# noise_monitor.net
KiCad netlist of a schematic drawn in EAGLE
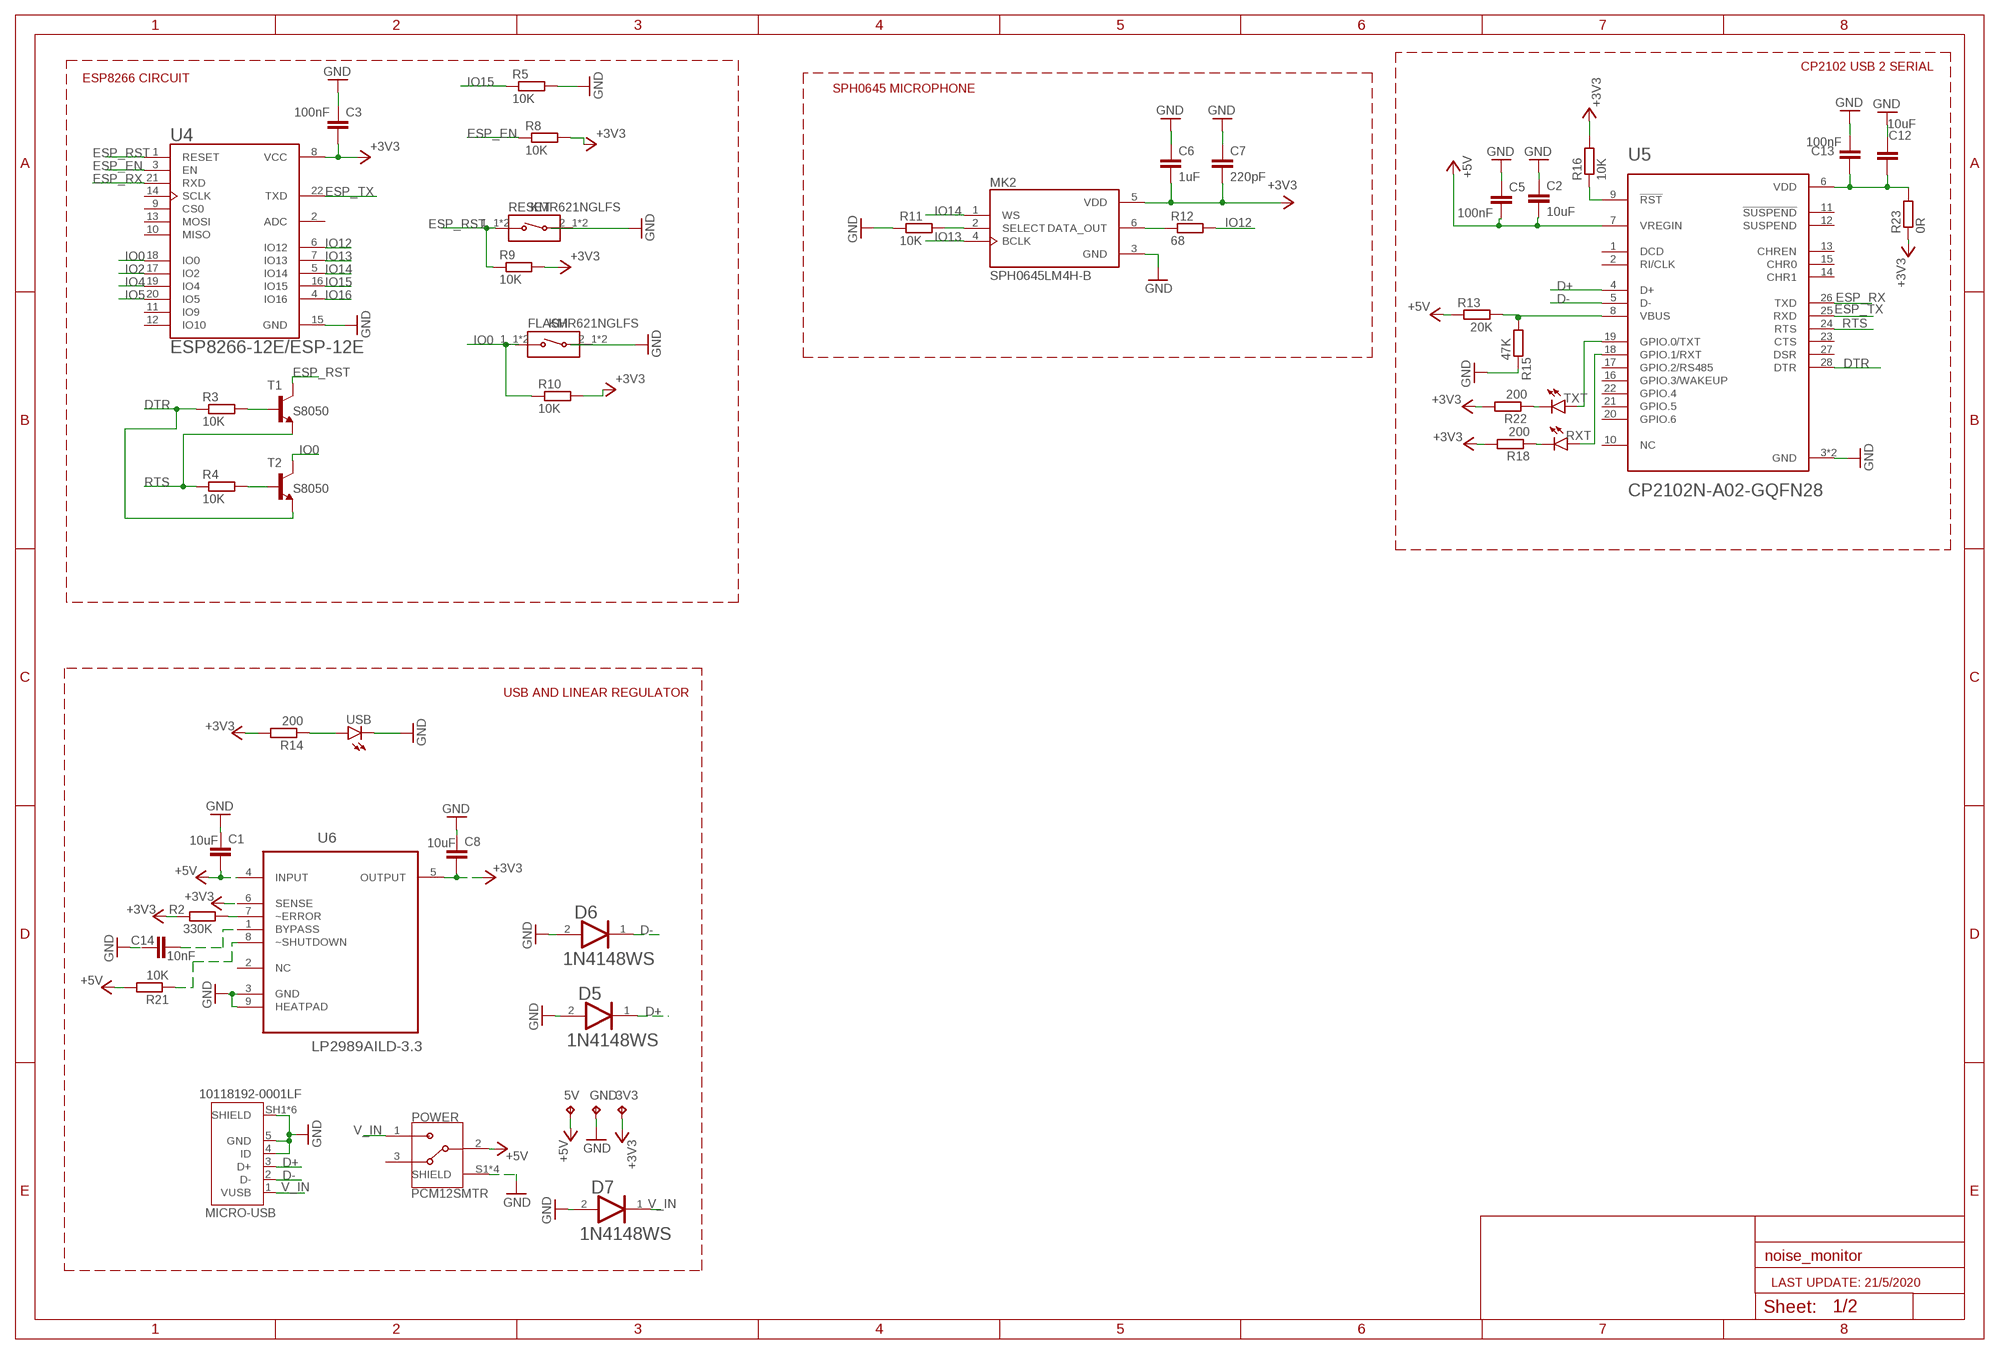
[diagram p0: schematic, sheet 1]
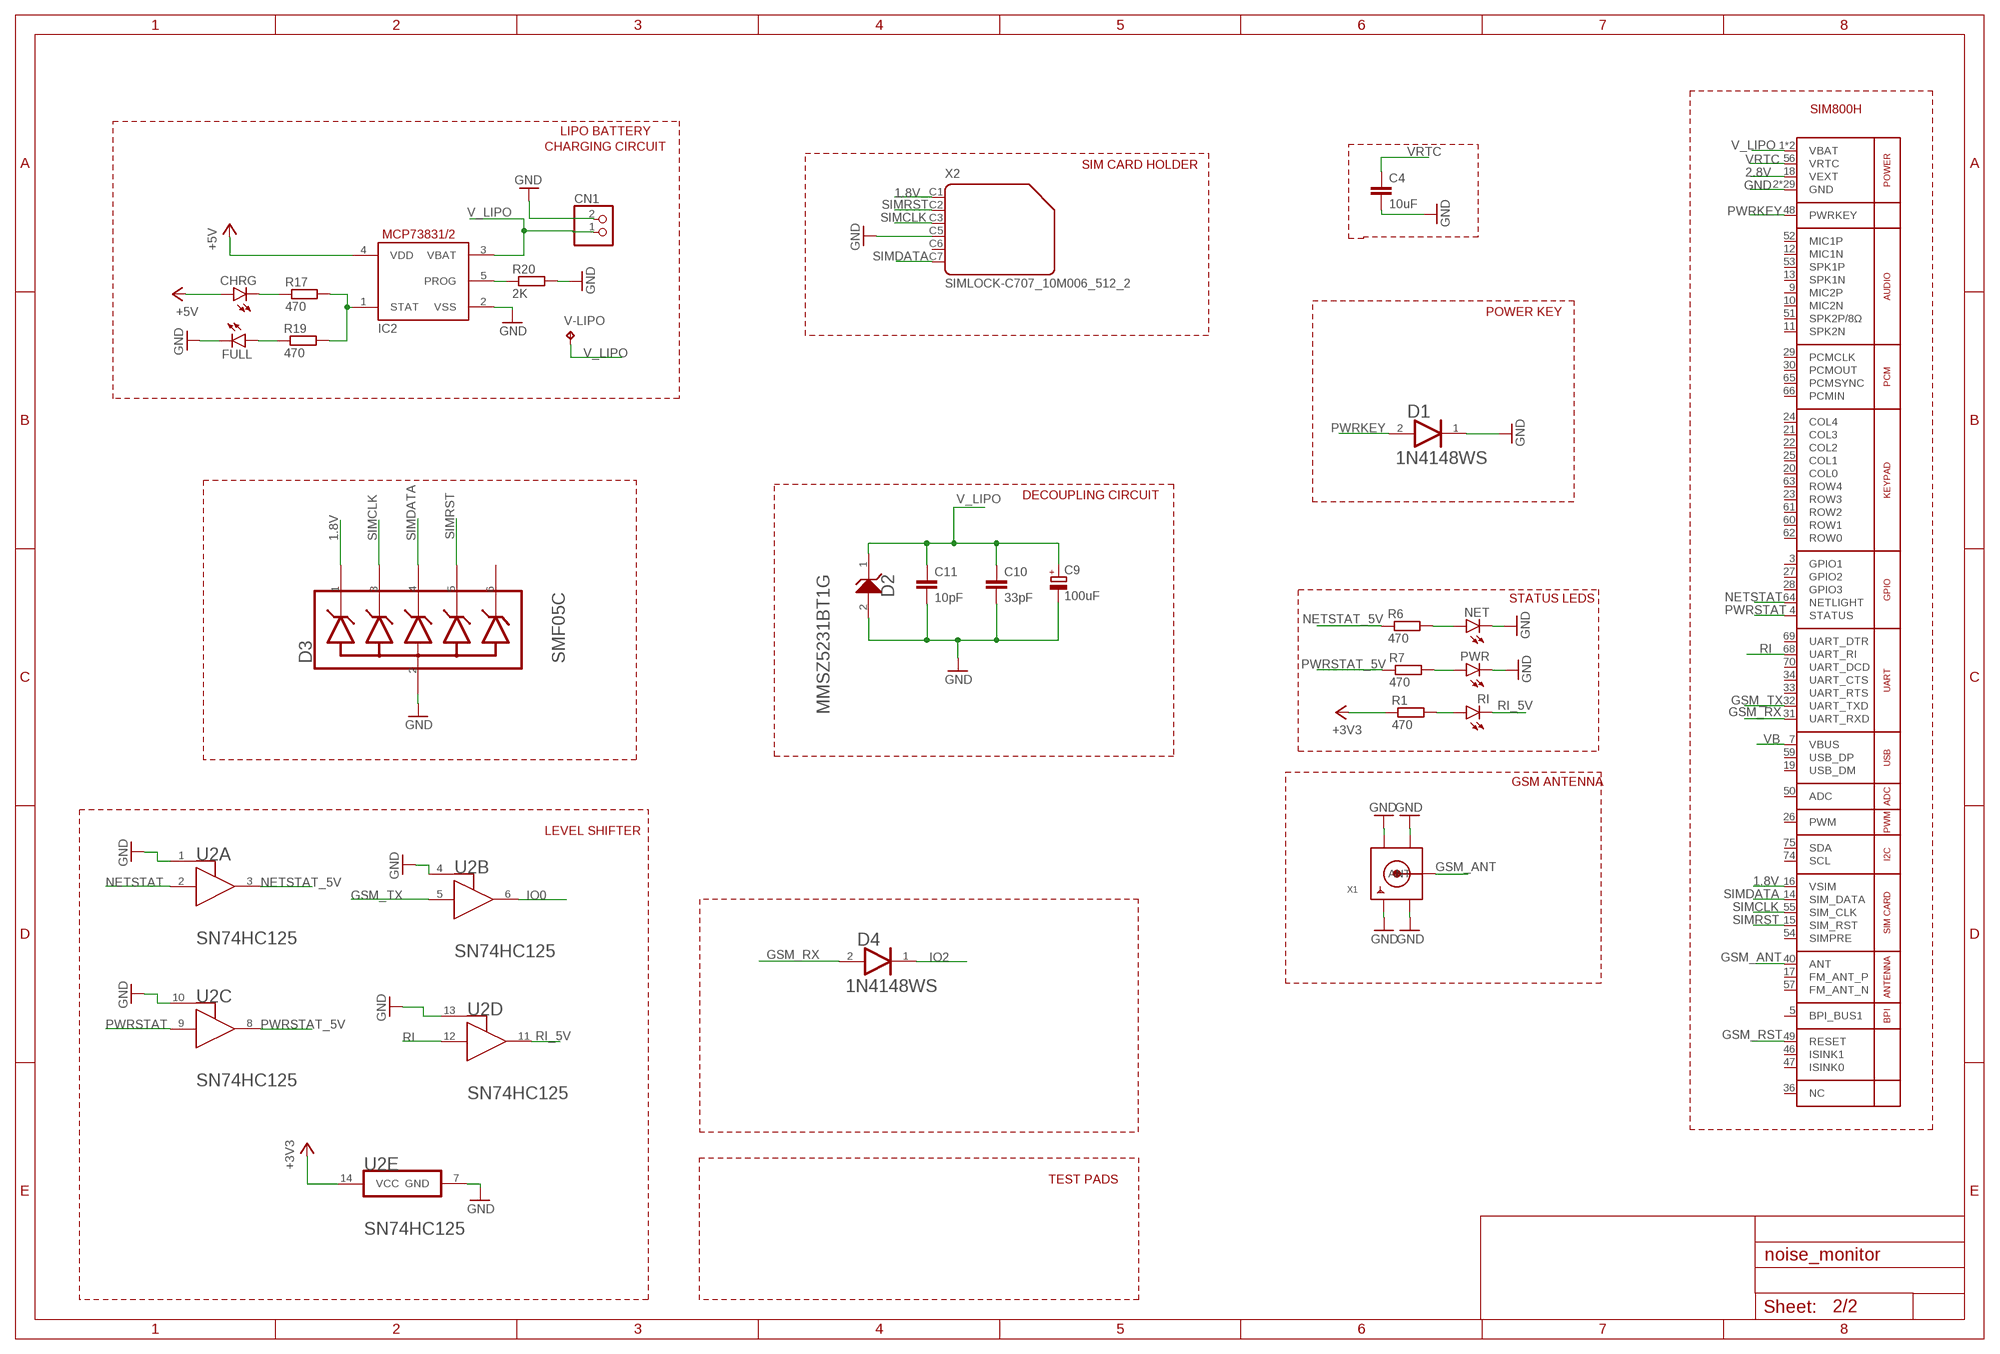
[diagram p1: schematic, sheet 2]

(export (version "E")
  (design (tool "Eeschema 10.0.6"))
  (components
    (comp (ref "C4")
      (value "10uF")
      (footprint "eagle-import:C0603")
      (libsource (lib "eagle-import") (part "C-EUC0603"))
    )
    (comp (ref "C9")
      (value "100uF")
      (footprint "eagle-import:PANASONIC_D")
      (libsource (lib "eagle-import") (part "CPOL-EUD"))
    )
    (comp (ref "C10")
      (value "33pF")
      (footprint "eagle-import:C0603")
      (libsource (lib "eagle-import") (part "C-EUC0603"))
    )
    (comp (ref "C11")
      (value "10pF")
      (footprint "eagle-import:C0603")
      (libsource (lib "eagle-import") (part "C-EUC0603"))
    )
    (comp (ref "CHRG")
      (value "LEDCHIP-LED0603")
      (footprint "eagle-import:CHIP-LED0603")
      (libsource (lib "eagle-import") (part "LEDCHIP-LED0603"))
    )
    (comp (ref "CN1")
      (value "JST_2PIN-SMT-RA")
      (footprint "eagle-import:JST-PH-2-SMT-RA")
      (libsource (lib "eagle-import") (part "JST_2PIN-SMT-RA"))
    )
    (comp (ref "D1")
      (value "ON_SEMI_1N4148WSON_SEMI_1N4148WS_0_0")
      (footprint "eagle-import:ON_SEMI_1N4148WS_0")
      (fields
        (field (name "DIGIKEY_PART_NUMBER") "1N4148WSFSCT-ND")
        (field (name "MF") "ON Semi")
        (field (name "MOUSER_PART_NUMBER") "512-1N4148WS")
      )
      (libsource (lib "eagle-import") (part "ON_SEMI_1N4148WSON_SEMI_1N4148WS_0_0"))
    )
    (comp (ref "D2")
      (value "ON_SEMICONDUCTOR_MMSZ5231BT1GON_SEMICONDUCTOR_MMSZ5231BT1G_0_0")
      (footprint "eagle-import:ON_SEMICONDUCTOR_MMSZ5231BT1G_0")
      (fields (field (name "MF") "On Semiconductor") (field (name "MPN") "MMSZ5231BT1G"))
      (libsource (lib "eagle-import") (part "ON_SEMICONDUCTOR_MMSZ5231BT1GON_SEMICONDUCTOR_MMSZ5231BT1G_0_0"))
    )
    (comp (ref "D3")
      (value "SEMTECH_SMF05CSEMTECH_SMF05C_0_0")
      (footprint "eagle-import:SEMTECH_SMF05C_0")
      (fields
        (field (name "DIGIKEY_PART_NUMBER") "SMF05CCT-ND")
        (field (name "MF") "Semtech")
        (field (name "MOUSER_PART_NUMBER") "947-SMF05C.TCT")
      )
      (libsource (lib "eagle-import") (part "SEMTECH_SMF05CSEMTECH_SMF05C_0_0"))
    )
    (comp (ref "D4")
      (value "ON_SEMI_1N4148WSON_SEMI_1N4148WS_0_0")
      (footprint "eagle-import:ON_SEMI_1N4148WS_0")
      (fields
        (field (name "DIGIKEY_PART_NUMBER") "1N4148WSFSCT-ND")
        (field (name "MF") "ON Semi")
        (field (name "MOUSER_PART_NUMBER") "512-1N4148WS")
      )
      (libsource (lib "eagle-import") (part "ON_SEMI_1N4148WSON_SEMI_1N4148WS_0_0"))
    )
    (comp (ref "FULL")
      (value "LEDCHIP-LED0603")
      (footprint "eagle-import:CHIP-LED0603")
      (libsource (lib "eagle-import") (part "LEDCHIP-LED0603"))
    )
    (comp (ref "IC2")
      (value "MCP73831/OT")
      (footprint "eagle-import:SOT23-5L")
      (libsource (lib "eagle-import") (part "MCP73831/OT"))
    )
    (comp (ref "NET")
      (value "LEDCHIP-LED0603")
      (footprint "eagle-import:CHIP-LED0603")
      (libsource (lib "eagle-import") (part "LEDCHIP-LED0603"))
    )
    (comp (ref "PWR")
      (value "LEDCHIP-LED0603")
      (footprint "eagle-import:CHIP-LED0603")
      (libsource (lib "eagle-import") (part "LEDCHIP-LED0603"))
    )
    (comp (ref "R1")
      (value "470")
      (footprint "eagle-import:R0603")
      (libsource (lib "eagle-import") (part "R-EU_R0603"))
    )
    (comp (ref "R6")
      (value "470")
      (footprint "eagle-import:R0603")
      (libsource (lib "eagle-import") (part "R-EU_R0603"))
    )
    (comp (ref "R7")
      (value "470")
      (footprint "eagle-import:R0603")
      (libsource (lib "eagle-import") (part "R-EU_R0603"))
    )
    (comp (ref "R17")
      (value "470")
      (footprint "eagle-import:R0603")
      (libsource (lib "eagle-import") (part "R-EU_R0603"))
    )
    (comp (ref "R19")
      (value "470")
      (footprint "eagle-import:R0603")
      (libsource (lib "eagle-import") (part "R-EU_R0603"))
    )
    (comp (ref "R20")
      (value "2K")
      (footprint "eagle-import:R0603")
      (libsource (lib "eagle-import") (part "R-EU_R0603"))
    )
    (comp (ref "RI")
      (value "LEDCHIP-LED0603")
      (footprint "eagle-import:CHIP-LED0603")
      (libsource (lib "eagle-import") (part "LEDCHIP-LED0603"))
    )
    (comp (ref "U1")
      (value "GSM_SIM800L")
      (footprint "eagle-import:SIM800L")
      (libsource (lib "eagle-import") (part "GSM_SIM800L"))
    )
    (comp (ref "U2")
      (value "TEXAS_INSTRUMENTS_SN74HC125TEXAS_INSTRUMENTS_SN74HC125_0_0")
      (footprint "eagle-import:TEXAS_INSTRUMENTS_SN74HC125_0")
      (fields (field (name "MF") "Texas Instruments") (field (name "MPN") "SN74HC125"))
      (libsource (lib "eagle-import") (part "TEXAS_INSTRUMENTS_SN74HC125TEXAS_INSTRUMENTS_SN74HC125_0_0"))
    )
    (comp (ref "V-LIPO")
      (value "TPTP06R")
      (footprint "eagle-import:TP06R")
      (libsource (lib "eagle-import") (part "TPTP06R"))
    )
    (comp (ref "X1")
      (value "SMACONNECTOR_EDGE_UFL")
      (footprint "eagle-import:SMA_EDGELAUNCH_UFL")
      (libsource (lib "eagle-import") (part "SMACONNECTOR_EDGE_UFL"))
    )
    (comp (ref "X2")
      (value "SIMLOCK-C707_10M006_512_2")
      (footprint "eagle-import:C707_10M006_512_2")
      (libsource (lib "eagle-import") (part "SIMLOCK-C707_10M006_512_2"))
    )
    (comp (ref "3V3")
      (value "TPTP06R")
      (footprint "eagle-import:TP06R")
      (libsource (lib "eagle-import") (part "TPTP06R"))
    )
    (comp (ref "5V")
      (value "TPTP06R")
      (footprint "eagle-import:TP06R")
      (libsource (lib "eagle-import") (part "TPTP06R"))
    )
    (comp (ref "C1")
      (value "10uF")
      (footprint "eagle-import:C0603")
      (libsource (lib "eagle-import") (part "C-EUC0603"))
    )
    (comp (ref "C2")
      (value "10uF")
      (footprint "eagle-import:C0603")
      (libsource (lib "eagle-import") (part "C-EUC0603"))
    )
    (comp (ref "C3")
      (value "100nF")
      (footprint "eagle-import:C0805")
      (libsource (lib "eagle-import") (part "C-EUC0805"))
    )
    (comp (ref "C5")
      (value "100nF")
      (footprint "eagle-import:C0805")
      (libsource (lib "eagle-import") (part "C-EUC0805"))
    )
    (comp (ref "C6")
      (value "1uF")
      (footprint "eagle-import:C0603")
      (libsource (lib "eagle-import") (part "C-EUC0603"))
    )
    (comp (ref "C7")
      (value "220pF")
      (footprint "eagle-import:C0603")
      (libsource (lib "eagle-import") (part "C-EUC0603"))
    )
    (comp (ref "C8")
      (value "10uF")
      (footprint "eagle-import:C0603")
      (libsource (lib "eagle-import") (part "C-EUC0603"))
    )
    (comp (ref "C12")
      (value "10uF")
      (footprint "eagle-import:C0603")
      (libsource (lib "eagle-import") (part "C-EUC0603"))
    )
    (comp (ref "C13")
      (value "100nF")
      (footprint "eagle-import:C0805")
      (libsource (lib "eagle-import") (part "C-EUC0805"))
    )
    (comp (ref "C14")
      (value "10nF")
      (footprint "eagle-import:C0603")
      (libsource (lib "eagle-import") (part "C-EUC0603"))
    )
    (comp (ref "D5")
      (value "ON_SEMI_1N4148WSON_SEMI_1N4148WS_0_0")
      (footprint "eagle-import:ON_SEMI_1N4148WS_0")
      (fields
        (field (name "DIGIKEY_PART_NUMBER") "1N4148WSFSCT-ND")
        (field (name "MF") "ON Semi")
        (field (name "MOUSER_PART_NUMBER") "512-1N4148WS")
      )
      (libsource (lib "eagle-import") (part "ON_SEMI_1N4148WSON_SEMI_1N4148WS_0_0"))
    )
    (comp (ref "D6")
      (value "ON_SEMI_1N4148WSON_SEMI_1N4148WS_0_0")
      (footprint "eagle-import:ON_SEMI_1N4148WS_0")
      (fields
        (field (name "DIGIKEY_PART_NUMBER") "1N4148WSFSCT-ND")
        (field (name "MF") "ON Semi")
        (field (name "MOUSER_PART_NUMBER") "512-1N4148WS")
      )
      (libsource (lib "eagle-import") (part "ON_SEMI_1N4148WSON_SEMI_1N4148WS_0_0"))
    )
    (comp (ref "D7")
      (value "ON_SEMI_1N4148WSON_SEMI_1N4148WS_0_0")
      (footprint "eagle-import:ON_SEMI_1N4148WS_0")
      (fields
        (field (name "DIGIKEY_PART_NUMBER") "1N4148WSFSCT-ND")
        (field (name "MF") "ON Semi")
        (field (name "MOUSER_PART_NUMBER") "512-1N4148WS")
      )
      (libsource (lib "eagle-import") (part "ON_SEMI_1N4148WSON_SEMI_1N4148WS_0_0"))
    )
    (comp (ref "FLASH")
      (value "KMR621NGLFS")
      (footprint "eagle-import:SW_KMR621NGLFS")
      (fields (field (name "MF") "C&K") (field (name "MP") "KMR621NG LFS"))
      (libsource (lib "eagle-import") (part "KMR621NGLFS"))
    )
    (comp (ref "GND")
      (value "TPTP06R")
      (footprint "eagle-import:TP06R")
      (libsource (lib "eagle-import") (part "TPTP06R"))
    )
    (comp (ref "MICRO-USB")
      (value "10118192-0001LF")
      (footprint "eagle-import:AMPHENOL_10118192-0001LF")
      (fields (field (name "MF") "Amphenol ICC"))
      (libsource (lib "eagle-import") (part "10118192-0001LF"))
    )
    (comp (ref "MK2")
      (value "SPH0645LM4H-B")
      (footprint "eagle-import:MIC_SPH0645LM4H-B")
      (fields (field (name "MF") "Knowles"))
      (libsource (lib "eagle-import") (part "SPH0645LM4H-B"))
    )
    (comp (ref "POWER")
      (value "PCM12SMTR")
      (footprint "eagle-import:SW_PCM12SMTR")
      (fields (field (name "MF") "C&K"))
      (libsource (lib "eagle-import") (part "PCM12SMTR"))
    )
    (comp (ref "R2")
      (value "330K")
      (footprint "eagle-import:R0603")
      (libsource (lib "eagle-import") (part "R-EU_R0603"))
    )
    (comp (ref "R3")
      (value "10K")
      (footprint "eagle-import:R0603")
      (libsource (lib "eagle-import") (part "R-EU_R0603"))
    )
    (comp (ref "R4")
      (value "10K")
      (footprint "eagle-import:R0603")
      (libsource (lib "eagle-import") (part "R-EU_R0603"))
    )
    (comp (ref "R5")
      (value "10K")
      (footprint "eagle-import:R0603")
      (libsource (lib "eagle-import") (part "R-EU_R0603"))
    )
    (comp (ref "R8")
      (value "10K")
      (footprint "eagle-import:R0603")
      (libsource (lib "eagle-import") (part "R-EU_R0603"))
    )
    (comp (ref "R9")
      (value "10K")
      (footprint "eagle-import:R0603")
      (libsource (lib "eagle-import") (part "R-EU_R0603"))
    )
    (comp (ref "R10")
      (value "10K")
      (footprint "eagle-import:R0603")
      (libsource (lib "eagle-import") (part "R-EU_R0603"))
    )
    (comp (ref "R11")
      (value "10K")
      (footprint "eagle-import:R0603")
      (libsource (lib "eagle-import") (part "R-EU_R0603"))
    )
    (comp (ref "R12")
      (value "68")
      (footprint "eagle-import:R0603")
      (libsource (lib "eagle-import") (part "R-EU_R0603"))
    )
    (comp (ref "R13")
      (value "20K")
      (footprint "eagle-import:R0603")
      (libsource (lib "eagle-import") (part "R-EU_R0603"))
    )
    (comp (ref "R14")
      (value "200")
      (footprint "eagle-import:R0603")
      (libsource (lib "eagle-import") (part "R-EU_R0603"))
    )
    (comp (ref "R15")
      (value "47K")
      (footprint "eagle-import:R0603")
      (libsource (lib "eagle-import") (part "R-EU_R0603"))
    )
    (comp (ref "R16")
      (value "10K")
      (footprint "eagle-import:R0603")
      (libsource (lib "eagle-import") (part "R-EU_R0603"))
    )
    (comp (ref "R18")
      (value "200")
      (footprint "eagle-import:R0603")
      (libsource (lib "eagle-import") (part "R-EU_R0603"))
    )
    (comp (ref "R21")
      (value "10K")
      (footprint "eagle-import:R0603")
      (libsource (lib "eagle-import") (part "R-EU_R0603"))
    )
    (comp (ref "R22")
      (value "200")
      (footprint "eagle-import:R0603")
      (libsource (lib "eagle-import") (part "R-EU_R0603"))
    )
    (comp (ref "R23")
      (value "0R")
      (footprint "eagle-import:R0201")
      (libsource (lib "eagle-import") (part "R-EU_R0201"))
    )
    (comp (ref "RESET")
      (value "KMR621NGLFS")
      (footprint "eagle-import:SW_KMR621NGLFS")
      (fields (field (name "MF") "C&K") (field (name "MP") "KMR621NG LFS"))
      (libsource (lib "eagle-import") (part "KMR621NGLFS"))
    )
    (comp (ref "RXT")
      (value "LEDCHIP-LED0603")
      (footprint "eagle-import:CHIP-LED0603")
      (libsource (lib "eagle-import") (part "LEDCHIP-LED0603"))
    )
    (comp (ref "T1")
      (value "S8050")
      (footprint "eagle-import:SC59-BEC")
      (libsource (lib "eagle-import") (part "-NPN-SC59-BECMMUN2214LT1"))
    )
    (comp (ref "T2")
      (value "S8050")
      (footprint "eagle-import:SC59-BEC")
      (libsource (lib "eagle-import") (part "-NPN-SC59-BECMMUN2214LT1"))
    )
    (comp (ref "TXT")
      (value "LEDCHIP-LED0603")
      (footprint "eagle-import:CHIP-LED0603")
      (libsource (lib "eagle-import") (part "LEDCHIP-LED0603"))
    )
    (comp (ref "U4")
      (value "ESP8266-12E/ESP-12E")
      (footprint "eagle-import:XCVR_ESP8266-12E_ESP-12E")
      (fields (field (name "MF") "AI-Thinker"))
      (libsource (lib "eagle-import") (part "ESP8266-12E/ESP-12E"))
    )
    (comp (ref "U5")
      (value "CP2102N-A02-GQFN28")
      (footprint "eagle-import:QFN50P500X500X80-29N")
      (fields (field (name "MF") "Silicon Labs"))
      (libsource (lib "eagle-import") (part "CP2102N-A02-GQFN28"))
    )
    (comp (ref "U6")
      (value "LP2989AILD-3.3")
      (footprint "eagle-import:DFN400X400X80-9N")
      (fields (field (name "MF") "Texas Instruments") (field (name "MP") "LP2989AILD-3.3/NOPB"))
      (libsource (lib "eagle-import") (part "LP2989AILD-3.3"))
    )
    (comp (ref "USB")
      (value "LEDCHIP-LED0603")
      (footprint "eagle-import:CHIP-LED0603")
      (libsource (lib "eagle-import") (part "LEDCHIP-LED0603"))
    )
  )
  (nets
    (net (code "1") (name "+3V3") (class "Default")
      (node (ref "3V3") (pin "TP") (pinfunction "TP_TP") (pintype "input"))
      (node (ref "C3") (pin "2") (pinfunction "2_2") (pintype "passive"))
      (node (ref "C6") (pin "2") (pinfunction "2_2") (pintype "passive"))
      (node (ref "C7") (pin "2") (pinfunction "2_2") (pintype "passive"))
      (node (ref "C8") (pin "2") (pinfunction "2_2") (pintype "passive"))
      (node (ref "MK2") (pin "5") (pinfunction "VDD_5") (pintype "power_in"))
      (node (ref "R1") (pin "1") (pinfunction "1_1") (pintype "passive"))
      (node (ref "R10") (pin "2") (pinfunction "2_2") (pintype "passive"))
      (node (ref "R14") (pin "2") (pinfunction "2_2") (pintype "passive"))
      (node (ref "R16") (pin "2") (pinfunction "2_2") (pintype "passive"))
      (node (ref "R18") (pin "2") (pinfunction "2_2") (pintype "passive"))
      (node (ref "R2") (pin "1") (pinfunction "1_1") (pintype "passive"))
      (node (ref "R22") (pin "2") (pinfunction "2_2") (pintype "passive"))
      (node (ref "R23") (pin "1") (pinfunction "1_1") (pintype "passive"))
      (node (ref "R8") (pin "2") (pinfunction "2_2") (pintype "passive"))
      (node (ref "R9") (pin "2") (pinfunction "2_2") (pintype "passive"))
      (node (ref "U2") (pin "14") (pinfunction "VCC_14") (pintype "power_in"))
      (node (ref "U4") (pin "8") (pinfunction "VCC_8") (pintype "power_in"))
      (node (ref "U6") (pin "5") (pinfunction "OUTPUT_5") (pintype "output"))
      (node (ref "U6") (pin "6") (pinfunction "SENSE_6") (pintype "input"))
    )
    (net (code "2") (name "+5V") (class "Default")
      (node (ref "5V") (pin "TP") (pinfunction "TP_TP") (pintype "input"))
      (node (ref "C1") (pin "2") (pinfunction "2_2") (pintype "passive"))
      (node (ref "C2") (pin "2") (pinfunction "2_2") (pintype "passive"))
      (node (ref "C5") (pin "2") (pinfunction "2_2") (pintype "passive"))
      (node (ref "CHRG") (pin "A") (pinfunction "A_A") (pintype "passive"))
      (node (ref "IC2") (pin "4") (pinfunction "VDD_4") (pintype "power_in"))
      (node (ref "POWER") (pin "2") (pinfunction "2_2") (pintype "passive"))
      (node (ref "R13") (pin "1") (pinfunction "1_1") (pintype "passive"))
      (node (ref "R21") (pin "2") (pinfunction "2_2") (pintype "passive"))
      (node (ref "U5") (pin "7") (pinfunction "VREGIN_7") (pintype "input"))
      (node (ref "U6") (pin "4") (pinfunction "INPUT_4") (pintype "power_in"))
    )
    (net (code "3") (name "1.8V") (class "Default")
      (node (ref "D3") (pin "1") (pinfunction "1_CATHODE_1") (pintype "bidirectional"))
      (node (ref "U1") (pin "16") (pinfunction "VSIM_16") (pintype "power_in"))
      (node (ref "X2") (pin "C1") (pinfunction "1_C1") (pintype "passive"))
    )
    (net (code "4") (name "2.8V") (class "Default")
      (node (ref "U1") (pin "18") (pinfunction "VEXT_18") (pintype "power_in"))
    )
    (net (code "5") (name "D+") (class "Default")
      (node (ref "D5") (pin "1") (pinfunction "CATHODE_1") (pintype "bidirectional"))
      (node (ref "MICRO-USB") (pin "3") (pinfunction "D+_3") (pintype "passive"))
      (node (ref "U5") (pin "4") (pinfunction "D+_4") (pintype "bidirectional"))
    )
    (net (code "6") (name "D-") (class "Default")
      (node (ref "D6") (pin "1") (pinfunction "CATHODE_1") (pintype "bidirectional"))
      (node (ref "MICRO-USB") (pin "2") (pinfunction "D-_2") (pintype "passive"))
      (node (ref "U5") (pin "5") (pinfunction "D-_5") (pintype "bidirectional"))
    )
    (net (code "7") (name "DTR") (class "Default")
      (node (ref "R3") (pin "1") (pinfunction "1_1") (pintype "passive"))
      (node (ref "T2") (pin "E") (pinfunction "E_E") (pintype "passive"))
      (node (ref "U5") (pin "28") (pinfunction "DTR_28") (pintype "output"))
    )
    (net (code "8") (name "ESP_EN") (class "Default")
      (node (ref "R8") (pin "1") (pinfunction "1_1") (pintype "passive"))
      (node (ref "U4") (pin "3") (pinfunction "EN_3") (pintype "input"))
    )
    (net (code "9") (name "ESP_RST") (class "Default")
      (node (ref "R9") (pin "1") (pinfunction "1_1") (pintype "passive"))
      (node (ref "RESET") (pin "1_1") (pinfunction "1_1_1") (pintype "passive"))
      (node (ref "RESET") (pin "1_2") (pinfunction "1_1_2") (pintype "passive"))
      (node (ref "T1") (pin "C") (pinfunction "C_C") (pintype "passive"))
      (node (ref "U4") (pin "1") (pinfunction "RESET_1") (pintype "input"))
    )
    (net (code "10") (name "ESP_RX") (class "Default")
      (node (ref "U4") (pin "21") (pinfunction "RXD_21") (pintype "input"))
      (node (ref "U5") (pin "26") (pinfunction "TXD_26") (pintype "output"))
    )
    (net (code "11") (name "ESP_TX") (class "Default")
      (node (ref "U4") (pin "22") (pinfunction "TXD_22") (pintype "output"))
      (node (ref "U5") (pin "25") (pinfunction "RXD_25") (pintype "input"))
    )
    (net (code "12") (name "GND") (class "Default")
      (node (ref "C1") (pin "1") (pinfunction "1_1") (pintype "passive"))
      (node (ref "C10") (pin "2") (pinfunction "2_2") (pintype "passive"))
      (node (ref "C11") (pin "2") (pinfunction "2_2") (pintype "passive"))
      (node (ref "C12") (pin "1") (pinfunction "1_1") (pintype "passive"))
      (node (ref "C13") (pin "1") (pinfunction "1_1") (pintype "passive"))
      (node (ref "C14") (pin "1") (pinfunction "1_1") (pintype "passive"))
      (node (ref "C2") (pin "1") (pinfunction "1_1") (pintype "passive"))
      (node (ref "C3") (pin "1") (pinfunction "1_1") (pintype "passive"))
      (node (ref "C4") (pin "2") (pinfunction "2_2") (pintype "passive"))
      (node (ref "C5") (pin "1") (pinfunction "1_1") (pintype "passive"))
      (node (ref "C6") (pin "1") (pinfunction "1_1") (pintype "passive"))
      (node (ref "C7") (pin "1") (pinfunction "1_1") (pintype "passive"))
      (node (ref "C8") (pin "1") (pinfunction "1_1") (pintype "passive"))
      (node (ref "C9") (pin "-") (pinfunction "-_-") (pintype "passive"))
      (node (ref "CN1") (pin "2") (pinfunction "1_2") (pintype "passive"))
      (node (ref "D1") (pin "1") (pinfunction "CATHODE_1") (pintype "bidirectional"))
      (node (ref "D2") (pin "2") (pinfunction "A_2") (pintype "passive"))
      (node (ref "D3") (pin "2") (pinfunction "ANODE_2") (pintype "bidirectional"))
      (node (ref "D5") (pin "2") (pinfunction "ANODE_2") (pintype "bidirectional"))
      (node (ref "D6") (pin "2") (pinfunction "ANODE_2") (pintype "bidirectional"))
      (node (ref "D7") (pin "2") (pinfunction "ANODE_2") (pintype "bidirectional"))
      (node (ref "FLASH") (pin "2_1") (pinfunction "2_2_1") (pintype "passive"))
      (node (ref "FLASH") (pin "2_2") (pinfunction "2_2_2") (pintype "passive"))
      (node (ref "FULL") (pin "C") (pinfunction "C_C") (pintype "passive"))
      (node (ref "GND") (pin "TP") (pinfunction "TP_TP") (pintype "input"))
      (node (ref "IC2") (pin "2") (pinfunction "VSS_2") (pintype "power_in"))
      (node (ref "MICRO-USB") (pin "4") (pinfunction "ID_4") (pintype "passive"))
      (node (ref "MICRO-USB") (pin "5") (pinfunction "GND_5") (pintype "passive"))
      (node (ref "MICRO-USB") (pin "SH1") (pinfunction "SHIELD_SH1") (pintype "passive"))
      (node (ref "MICRO-USB") (pin "SH2") (pinfunction "SHIELD_SH2") (pintype "passive"))
      (node (ref "MICRO-USB") (pin "SH3") (pinfunction "SHIELD_SH3") (pintype "passive"))
      (node (ref "MICRO-USB") (pin "SH4") (pinfunction "SHIELD_SH4") (pintype "passive"))
      (node (ref "MICRO-USB") (pin "SH5") (pinfunction "SHIELD_SH5") (pintype "passive"))
      (node (ref "MICRO-USB") (pin "SH6") (pinfunction "SHIELD_SH6") (pintype "passive"))
      (node (ref "MK2") (pin "3") (pinfunction "GND_3") (pintype "power_in"))
      (node (ref "NET") (pin "C") (pinfunction "C_C") (pintype "passive"))
      (node (ref "POWER") (pin "S1") (pinfunction "SHIELD_S1") (pintype "passive"))
      (node (ref "POWER") (pin "S2") (pinfunction "SHIELD_S2") (pintype "passive"))
      (node (ref "POWER") (pin "S3") (pinfunction "SHIELD_S3") (pintype "passive"))
      (node (ref "POWER") (pin "S4") (pinfunction "SHIELD_S4") (pintype "passive"))
      (node (ref "PWR") (pin "C") (pinfunction "C_C") (pintype "passive"))
      (node (ref "R11") (pin "1") (pinfunction "1_1") (pintype "passive"))
      (node (ref "R15") (pin "2") (pinfunction "2_2") (pintype "passive"))
      (node (ref "R20") (pin "2") (pinfunction "2_2") (pintype "passive"))
      (node (ref "R5") (pin "2") (pinfunction "2_2") (pintype "passive"))
      (node (ref "RESET") (pin "2_1") (pinfunction "2_2_1") (pintype "passive"))
      (node (ref "RESET") (pin "2_2") (pinfunction "2_2_2") (pintype "passive"))
      (node (ref "U1") (pin "2") (pinfunction "GND_2") (pintype "power_in"))
      (node (ref "U1") (pin "35") (pinfunction "GND_35") (pintype "power_in"))
      (node (ref "U1") (pin "37") (pinfunction "GND_37") (pintype "power_in"))
      (node (ref "U1") (pin "38") (pinfunction "GND_38") (pintype "power_in"))
      (node (ref "U1") (pin "39") (pinfunction "GND_39") (pintype "power_in"))
      (node (ref "U1") (pin "41") (pinfunction "GND_41") (pintype "power_in"))
      (node (ref "U1") (pin "43") (pinfunction "GND_43") (pintype "power_in"))
      (node (ref "U1") (pin "44") (pinfunction "GND_44") (pintype "power_in"))
      (node (ref "U1") (pin "45") (pinfunction "GND_45") (pintype "power_in"))
      (node (ref "U1") (pin "58") (pinfunction "GND_58") (pintype "power_in"))
      (node (ref "U1") (pin "6") (pinfunction "GND_6") (pintype "power_in"))
      (node (ref "U1") (pin "67") (pinfunction "GND_67") (pintype "power_in"))
      (node (ref "U1") (pin "71") (pinfunction "GND_71") (pintype "power_in"))
      (node (ref "U1") (pin "72") (pinfunction "GND_72") (pintype "power_in"))
      (node (ref "U1") (pin "73") (pinfunction "GND_73") (pintype "power_in"))
      (node (ref "U1") (pin "76") (pinfunction "GND_76") (pintype "power_in"))
      (node (ref "U1") (pin "77") (pinfunction "GND_77") (pintype "power_in"))
      (node (ref "U1") (pin "78") (pinfunction "GND_78") (pintype "power_in"))
      (node (ref "U1") (pin "79") (pinfunction "GND_79") (pintype "power_in"))
      (node (ref "U1") (pin "8") (pinfunction "GND_8") (pintype "power_in"))
      (node (ref "U1") (pin "80") (pinfunction "GND_80") (pintype "power_in"))
      (node (ref "U1") (pin "81") (pinfunction "GND_81") (pintype "power_in"))
      (node (ref "U1") (pin "82") (pinfunction "GND_82") (pintype "power_in"))
      (node (ref "U1") (pin "83") (pinfunction "GND_83") (pintype "power_in"))
      (node (ref "U1") (pin "84") (pinfunction "GND_84") (pintype "power_in"))
      (node (ref "U1") (pin "85") (pinfunction "GND_85") (pintype "power_in"))
      (node (ref "U1") (pin "86") (pinfunction "GND_86") (pintype "power_in"))
      (node (ref "U1") (pin "87") (pinfunction "GND_87") (pintype "power_in"))
      (node (ref "U1") (pin "88") (pinfunction "GND_88") (pintype "power_in"))
      (node (ref "U2") (pin "1") (pinfunction "1_~{OE}_1") (pintype "input"))
      (node (ref "U2") (pin "10") (pinfunction "2_~{OE}_10") (pintype "input"))
      (node (ref "U2") (pin "13") (pinfunction "3_~{OE}_13") (pintype "input"))
      (node (ref "U2") (pin "4") (pinfunction "4_~{OE}_4") (pintype "input"))
      (node (ref "U2") (pin "7") (pinfunction "GND_7") (pintype "power_in"))
      (node (ref "U4") (pin "15") (pinfunction "GND_15") (pintype "power_in"))
      (node (ref "U5") (pin "29") (pinfunction "GND_29") (pintype "power_in"))
      (node (ref "U5") (pin "3") (pinfunction "GND_3") (pintype "power_in"))
      (node (ref "U6") (pin "3") (pinfunction "GND_3") (pintype "passive"))
      (node (ref "U6") (pin "9") (pinfunction "HEATPAD_9") (pintype "passive"))
      (node (ref "USB") (pin "C") (pinfunction "C_C") (pintype "passive"))
      (node (ref "X1") (pin "GND@1") (pinfunction "GND1_GND@1") (pintype "power_in"))
      (node (ref "X1") (pin "GND@2") (pinfunction "GND2_GND@2") (pintype "power_in"))
      (node (ref "X1") (pin "GND@3") (pinfunction "GND3_GND@3") (pintype "power_in"))
      (node (ref "X1") (pin "GND@4") (pinfunction "GND4_GND@4") (pintype "power_in"))
      (node (ref "X2") (pin "C5") (pinfunction "4_C5") (pintype "passive"))
    )
    (net (code "13") (name "GSM_ANT") (class "Default")
      (node (ref "U1") (pin "40") (pinfunction "ANT_40") (pintype "bidirectional"))
      (node (ref "X1") (pin "P") (pinfunction "ANT_P") (pintype "bidirectional"))
    )
    (net (code "14") (name "GSM_RST") (class "Default")
      (node (ref "U1") (pin "49") (pinfunction "RESET_49") (pintype "input"))
    )
    (net (code "15") (name "GSM_RX") (class "Default")
      (node (ref "D4") (pin "2") (pinfunction "ANODE_2") (pintype "bidirectional"))
      (node (ref "U1") (pin "31") (pinfunction "UART_RXD_31") (pintype "input"))
    )
    (net (code "16") (name "GSM_TX") (class "Default")
      (node (ref "U1") (pin "32") (pinfunction "UART_TXD_32") (pintype "output"))
      (node (ref "U2") (pin "5") (pinfunction "2A_5") (pintype "input"))
    )
    (net (code "17") (name "IO0") (class "Default")
      (node (ref "FLASH") (pin "1_1") (pinfunction "1_1_1") (pintype "passive"))
      (node (ref "FLASH") (pin "1_2") (pinfunction "1_1_2") (pintype "passive"))
      (node (ref "R10") (pin "1") (pinfunction "1_1") (pintype "passive"))
      (node (ref "T2") (pin "C") (pinfunction "C_C") (pintype "passive"))
      (node (ref "U2") (pin "6") (pinfunction "2Y_6") (pintype "tri_state"))
      (node (ref "U4") (pin "18") (pinfunction "IO0_18") (pintype "bidirectional"))
    )
    (net (code "18") (name "IO2") (class "Default")
      (node (ref "D4") (pin "1") (pinfunction "CATHODE_1") (pintype "bidirectional"))
      (node (ref "U4") (pin "17") (pinfunction "IO2_17") (pintype "bidirectional"))
    )
    (net (code "19") (name "IO4") (class "Default")
      (node (ref "U4") (pin "19") (pinfunction "IO4_19") (pintype "bidirectional"))
    )
    (net (code "20") (name "IO5") (class "Default")
      (node (ref "U4") (pin "20") (pinfunction "IO5_20") (pintype "bidirectional"))
    )
    (net (code "21") (name "IO12") (class "Default")
      (node (ref "R12") (pin "2") (pinfunction "2_2") (pintype "passive"))
      (node (ref "U4") (pin "6") (pinfunction "IO12_6") (pintype "bidirectional"))
    )
    (net (code "22") (name "IO13") (class "Default")
      (node (ref "MK2") (pin "4") (pinfunction "BCLK_4") (pintype "input"))
      (node (ref "U4") (pin "7") (pinfunction "IO13_7") (pintype "bidirectional"))
    )
    (net (code "23") (name "IO14") (class "Default")
      (node (ref "MK2") (pin "1") (pinfunction "WS_1") (pintype "input"))
      (node (ref "U4") (pin "5") (pinfunction "IO14_5") (pintype "bidirectional"))
    )
    (net (code "24") (name "IO15") (class "Default")
      (node (ref "R5") (pin "1") (pinfunction "1_1") (pintype "passive"))
      (node (ref "U4") (pin "16") (pinfunction "IO15_16") (pintype "bidirectional"))
    )
    (net (code "25") (name "IO16") (class "Default")
      (node (ref "U4") (pin "4") (pinfunction "IO16_4") (pintype "bidirectional"))
    )
    (net (code "26") (name "NETSTAT") (class "Default")
      (node (ref "U1") (pin "64") (pinfunction "NETLIGHT_64") (pintype "output"))
      (node (ref "U2") (pin "2") (pinfunction "1A_2") (pintype "input"))
    )
    (net (code "27") (name "NETSTAT_5V") (class "Default")
      (node (ref "R6") (pin "1") (pinfunction "1_1") (pintype "passive"))
      (node (ref "U2") (pin "3") (pinfunction "1Y_3") (pintype "tri_state"))
    )
    (net (code "28") (name "Net-(CHRG-PadC)") (class "Default")
      (node (ref "CHRG") (pin "C") (pinfunction "C_C") (pintype "passive"))
      (node (ref "R17") (pin "1") (pinfunction "1_1") (pintype "passive"))
    )
    (net (code "29") (name "Net-(FULL-PadA)") (class "Default")
      (node (ref "FULL") (pin "A") (pinfunction "A_A") (pintype "passive"))
      (node (ref "R19") (pin "1") (pinfunction "1_1") (pintype "passive"))
    )
    (net (code "30") (name "Net-(IC2-PROG)") (class "Default")
      (node (ref "IC2") (pin "5") (pinfunction "PROG_5") (pintype "input"))
      (node (ref "R20") (pin "1") (pinfunction "1_1") (pintype "passive"))
    )
    (net (code "31") (name "Net-(IC2-STAT)") (class "Default")
      (node (ref "IC2") (pin "1") (pinfunction "STAT_1") (pintype "output"))
      (node (ref "R17") (pin "2") (pinfunction "2_2") (pintype "passive"))
      (node (ref "R19") (pin "2") (pinfunction "2_2") (pintype "passive"))
    )
    (net (code "32") (name "Net-(MK2-DATA_OUT)") (class "Default")
      (node (ref "MK2") (pin "6") (pinfunction "DATA_OUT_6") (pintype "output"))
      (node (ref "R12") (pin "1") (pinfunction "1_1") (pintype "passive"))
    )
    (net (code "33") (name "Net-(MK2-SELECT)") (class "Default")
      (node (ref "MK2") (pin "2") (pinfunction "SELECT_2") (pintype "input"))
      (node (ref "R11") (pin "2") (pinfunction "2_2") (pintype "passive"))
    )
    (net (code "34") (name "Net-(NET-PadA)") (class "Default")
      (node (ref "NET") (pin "A") (pinfunction "A_A") (pintype "passive"))
      (node (ref "R6") (pin "2") (pinfunction "2_2") (pintype "passive"))
    )
    (net (code "35") (name "Net-(PWR-PadA)") (class "Default")
      (node (ref "PWR") (pin "A") (pinfunction "A_A") (pintype "passive"))
      (node (ref "R7") (pin "2") (pinfunction "2_2") (pintype "passive"))
    )
    (net (code "36") (name "Net-(R1-Pad2)") (class "Default")
      (node (ref "R1") (pin "2") (pinfunction "2_2") (pintype "passive"))
      (node (ref "RI") (pin "A") (pinfunction "A_A") (pintype "passive"))
    )
    (net (code "37") (name "Net-(R3-Pad2)") (class "Default")
      (node (ref "R3") (pin "2") (pinfunction "2_2") (pintype "passive"))
      (node (ref "T1") (pin "B") (pinfunction "B_B") (pintype "passive"))
    )
    (net (code "38") (name "Net-(R4-Pad2)") (class "Default")
      (node (ref "R4") (pin "2") (pinfunction "2_2") (pintype "passive"))
      (node (ref "T2") (pin "B") (pinfunction "B_B") (pintype "passive"))
    )
    (net (code "39") (name "Net-(R14-Pad1)") (class "Default")
      (node (ref "R14") (pin "1") (pinfunction "1_1") (pintype "passive"))
      (node (ref "USB") (pin "A") (pinfunction "A_A") (pintype "passive"))
    )
    (net (code "40") (name "Net-(R18-Pad1)") (class "Default")
      (node (ref "R18") (pin "1") (pinfunction "1_1") (pintype "passive"))
      (node (ref "RXT") (pin "C") (pinfunction "C_C") (pintype "passive"))
    )
    (net (code "41") (name "Net-(R22-Pad1)") (class "Default")
      (node (ref "R22") (pin "1") (pinfunction "1_1") (pintype "passive"))
      (node (ref "TXT") (pin "C") (pinfunction "C_C") (pintype "passive"))
    )
    (net (code "42") (name "Net-(U5-GPIO.0{slash}TXT)") (class "Default")
      (node (ref "TXT") (pin "A") (pinfunction "A_A") (pintype "passive"))
      (node (ref "U5") (pin "19") (pinfunction "GPIO.0/TXT_19") (pintype "bidirectional"))
    )
    (net (code "43") (name "Net-(U5-GPIO.1{slash}RXT)") (class "Default")
      (node (ref "RXT") (pin "A") (pinfunction "A_A") (pintype "passive"))
      (node (ref "U5") (pin "18") (pinfunction "GPIO.1/RXT_18") (pintype "bidirectional"))
    )
    (net (code "44") (name "Net-(U5-VBUS)") (class "Default")
      (node (ref "R13") (pin "2") (pinfunction "2_2") (pintype "passive"))
      (node (ref "R15") (pin "1") (pinfunction "1_1") (pintype "passive"))
      (node (ref "U5") (pin "8") (pinfunction "VBUS_8") (pintype "input"))
    )
    (net (code "45") (name "Net-(U5-VDD)") (class "Default")
      (node (ref "C12") (pin "2") (pinfunction "2_2") (pintype "passive"))
      (node (ref "C13") (pin "2") (pinfunction "2_2") (pintype "passive"))
      (node (ref "R23") (pin "2") (pinfunction "2_2") (pintype "passive"))
      (node (ref "U5") (pin "6") (pinfunction "VDD_6") (pintype "power_in"))
    )
    (net (code "46") (name "Net-(U5-~{RST})") (class "Default")
      (node (ref "R16") (pin "1") (pinfunction "1_1") (pintype "passive"))
      (node (ref "U5") (pin "9") (pinfunction "~{RST}_9") (pintype "input"))
    )
    (net (code "47") (name "Net-(U6-BYPASS)") (class "Default")
      (node (ref "C14") (pin "2") (pinfunction "2_2") (pintype "passive"))
      (node (ref "U6") (pin "1") (pinfunction "BYPASS_1") (pintype "input"))
    )
    (net (code "48") (name "Net-(U6-~{ERROR})") (class "Default")
      (node (ref "R2") (pin "2") (pinfunction "2_2") (pintype "passive"))
      (node (ref "U6") (pin "7") (pinfunction "~{ERROR}_7") (pintype "input"))
    )
    (net (code "49") (name "Net-(U6-~{SHUTDOWN})") (class "Default")
      (node (ref "R21") (pin "1") (pinfunction "1_1") (pintype "passive"))
      (node (ref "U6") (pin "8") (pinfunction "~{SHUTDOWN}_8") (pintype "input"))
    )
    (net (code "50") (name "PWRKEY") (class "Default")
      (node (ref "D1") (pin "2") (pinfunction "ANODE_2") (pintype "bidirectional"))
      (node (ref "U1") (pin "48") (pinfunction "PWRKEY_48") (pintype "input"))
    )
    (net (code "51") (name "PWRSTAT") (class "Default")
      (node (ref "U1") (pin "4") (pinfunction "STATUS_4") (pintype "output"))
      (node (ref "U2") (pin "9") (pinfunction "3A_9") (pintype "input"))
    )
    (net (code "52") (name "PWRSTAT_5V") (class "Default")
      (node (ref "R7") (pin "1") (pinfunction "1_1") (pintype "passive"))
      (node (ref "U2") (pin "8") (pinfunction "3Y_8") (pintype "tri_state"))
    )
    (net (code "53") (name "RI") (class "Default")
      (node (ref "U1") (pin "68") (pinfunction "UART_RI_68") (pintype "output"))
      (node (ref "U2") (pin "12") (pinfunction "4A_12") (pintype "input"))
    )
    (net (code "54") (name "RI_5V") (class "Default")
      (node (ref "RI") (pin "C") (pinfunction "C_C") (pintype "passive"))
      (node (ref "U2") (pin "11") (pinfunction "4Y_11") (pintype "tri_state"))
    )
    (net (code "55") (name "RTS") (class "Default")
      (node (ref "R4") (pin "1") (pinfunction "1_1") (pintype "passive"))
      (node (ref "T1") (pin "E") (pinfunction "E_E") (pintype "passive"))
      (node (ref "U5") (pin "24") (pinfunction "RTS_24") (pintype "output"))
    )
    (net (code "56") (name "SIMCLK") (class "Default")
      (node (ref "D3") (pin "3") (pinfunction "2_CATHODE_3") (pintype "bidirectional"))
      (node (ref "U1") (pin "55") (pinfunction "SIM_CLK_55") (pintype "output"))
      (node (ref "X2") (pin "C3") (pinfunction "3_C3") (pintype "passive"))
    )
    (net (code "57") (name "SIMDATA") (class "Default")
      (node (ref "D3") (pin "4") (pinfunction "3_CATHODE_4") (pintype "bidirectional"))
      (node (ref "U1") (pin "14") (pinfunction "SIM_DATA_14") (pintype "bidirectional"))
      (node (ref "X2") (pin "C7") (pinfunction "6_C7") (pintype "passive"))
    )
    (net (code "58") (name "SIMRST") (class "Default")
      (node (ref "D3") (pin "5") (pinfunction "4_CATHODE_5") (pintype "bidirectional"))
      (node (ref "U1") (pin "15") (pinfunction "SIM_RST_15") (pintype "output"))
      (node (ref "X2") (pin "C2") (pinfunction "2_C2") (pintype "passive"))
    )
    (net (code "59") (name "VB") (class "Default")
      (node (ref "U1") (pin "7") (pinfunction "VBUS_7") (pintype "power_in"))
    )
    (net (code "60") (name "VRTC") (class "Default")
      (node (ref "C4") (pin "1") (pinfunction "1_1") (pintype "passive"))
      (node (ref "U1") (pin "56") (pinfunction "VRTC_56") (pintype "power_in"))
    )
    (net (code "61") (name "V_IN") (class "Default")
      (node (ref "D7") (pin "1") (pinfunction "CATHODE_1") (pintype "bidirectional"))
      (node (ref "MICRO-USB") (pin "1") (pinfunction "VUSB_1") (pintype "passive"))
      (node (ref "POWER") (pin "1") (pinfunction "1_1") (pintype "passive"))
    )
    (net (code "62") (name "V_LIPO") (class "Default")
      (node (ref "C10") (pin "1") (pinfunction "1_1") (pintype "passive"))
      (node (ref "C11") (pin "1") (pinfunction "1_1") (pintype "passive"))
      (node (ref "C9") (pin "+") (pinfunction "+_+") (pintype "passive"))
      (node (ref "CN1") (pin "1") (pinfunction "2_1") (pintype "passive"))
      (node (ref "D2") (pin "1") (pinfunction "K_1") (pintype "passive"))
      (node (ref "IC2") (pin "3") (pinfunction "VBAT_3") (pintype "bidirectional"))
      (node (ref "U1") (pin "1") (pinfunction "VBAT_1") (pintype "power_in"))
      (node (ref "U1") (pin "42") (pinfunction "VBAT_42") (pintype "power_in"))
      (node (ref "V-LIPO") (pin "TP") (pinfunction "TP_TP") (pintype "input"))
    )
    (net (code "63") (name "unconnected-(D3-5_CATHODE-Pad6)") (class "Default")
      (node (ref "D3") (pin "6") (pinfunction "5_CATHODE_6") (pintype "bidirectional"))
    )
    (net (code "64") (name "unconnected-(POWER-Pad3)") (class "Default")
      (node (ref "POWER") (pin "3") (pinfunction "3_3") (pintype "passive"))
    )
    (net (code "65") (name "unconnected-(U1-ADC-Pad50)") (class "Default")
      (node (ref "U1") (pin "50") (pinfunction "ADC_50") (pintype "input"))
    )
    (net (code "66") (name "unconnected-(U1-BPI_BUS1-Pad5)") (class "Default")
      (node (ref "U1") (pin "5") (pinfunction "BPI_BUS1_5") (pintype "output"))
    )
    (net (code "67") (name "unconnected-(U1-COL0-Pad20)") (class "Default")
      (node (ref "U1") (pin "20") (pinfunction "COL0_20") (pintype "bidirectional"))
    )
    (net (code "68") (name "unconnected-(U1-COL1-Pad25)") (class "Default")
      (node (ref "U1") (pin "25") (pinfunction "COL1_25") (pintype "bidirectional"))
    )
    (net (code "69") (name "unconnected-(U1-COL2-Pad22)") (class "Default")
      (node (ref "U1") (pin "22") (pinfunction "COL2_22") (pintype "bidirectional"))
    )
    (net (code "70") (name "unconnected-(U1-COL3-Pad21)") (class "Default")
      (node (ref "U1") (pin "21") (pinfunction "COL3_21") (pintype "bidirectional"))
    )
    (net (code "71") (name "unconnected-(U1-COL4-Pad24)") (class "Default")
      (node (ref "U1") (pin "24") (pinfunction "COL4_24") (pintype "bidirectional"))
    )
    (net (code "72") (name "unconnected-(U1-FM_ANT_N-Pad57)") (class "Default")
      (node (ref "U1") (pin "57") (pinfunction "FM_ANT_N_57") (pintype "bidirectional"))
    )
    (net (code "73") (name "unconnected-(U1-FM_ANT_P-Pad17)") (class "Default")
      (node (ref "U1") (pin "17") (pinfunction "FM_ANT_P_17") (pintype "bidirectional"))
    )
    (net (code "74") (name "unconnected-(U1-GPIO1-Pad3)") (class "Default")
      (node (ref "U1") (pin "3") (pinfunction "GPIO1_3") (pintype "bidirectional"))
    )
    (net (code "75") (name "unconnected-(U1-GPIO2-Pad27)") (class "Default")
      (node (ref "U1") (pin "27") (pinfunction "GPIO2_27") (pintype "bidirectional"))
    )
    (net (code "76") (name "unconnected-(U1-GPIO3-Pad28)") (class "Default")
      (node (ref "U1") (pin "28") (pinfunction "GPIO3_28") (pintype "bidirectional"))
    )
    (net (code "77") (name "unconnected-(U1-ISINK0-Pad47)") (class "Default")
      (node (ref "U1") (pin "47") (pinfunction "ISINK0_47") (pintype "input"))
    )
    (net (code "78") (name "unconnected-(U1-ISINK1-Pad46)") (class "Default")
      (node (ref "U1") (pin "46") (pinfunction "ISINK1_46") (pintype "input"))
    )
    (net (code "79") (name "unconnected-(U1-MIC1N-Pad12)") (class "Default")
      (node (ref "U1") (pin "12") (pinfunction "MIC1N_12") (pintype "input"))
    )
    (net (code "80") (name "unconnected-(U1-MIC1P-Pad52)") (class "Default")
      (node (ref "U1") (pin "52") (pinfunction "MIC1P_52") (pintype "input"))
    )
    (net (code "81") (name "unconnected-(U1-MIC2N-Pad10)") (class "Default")
      (node (ref "U1") (pin "10") (pinfunction "MIC2N_10") (pintype "input"))
    )
    (net (code "82") (name "unconnected-(U1-MIC2P-Pad9)") (class "Default")
      (node (ref "U1") (pin "9") (pinfunction "MIC2P_9") (pintype "input"))
    )
    (net (code "83") (name "unconnected-(U1-NC-Pad36)") (class "Default")
      (node (ref "U1") (pin "36") (pinfunction "NC_36") (pintype "no_connect"))
    )
    (net (code "84") (name "unconnected-(U1-PCMCLK-Pad29)") (class "Default")
      (node (ref "U1") (pin "29") (pinfunction "PCMCLK_29") (pintype "output"))
    )
    (net (code "85") (name "unconnected-(U1-PCMIN-Pad66)") (class "Default")
      (node (ref "U1") (pin "66") (pinfunction "PCMIN_66") (pintype "input"))
    )
    (net (code "86") (name "unconnected-(U1-PCMOUT-Pad30)") (class "Default")
      (node (ref "U1") (pin "30") (pinfunction "PCMOUT_30") (pintype "output"))
    )
    (net (code "87") (name "unconnected-(U1-PCMSYNC-Pad65)") (class "Default")
      (node (ref "U1") (pin "65") (pinfunction "PCMSYNC_65") (pintype "output"))
    )
    (net (code "88") (name "unconnected-(U1-PWM-Pad26)") (class "Default")
      (node (ref "U1") (pin "26") (pinfunction "PWM_26") (pintype "output"))
    )
    (net (code "89") (name "unconnected-(U1-ROW0-Pad62)") (class "Default")
      (node (ref "U1") (pin "62") (pinfunction "ROW0_62") (pintype "bidirectional"))
    )
    (net (code "90") (name "unconnected-(U1-ROW1-Pad60)") (class "Default")
      (node (ref "U1") (pin "60") (pinfunction "ROW1_60") (pintype "bidirectional"))
    )
    (net (code "91") (name "unconnected-(U1-ROW2-Pad61)") (class "Default")
      (node (ref "U1") (pin "61") (pinfunction "ROW2_61") (pintype "bidirectional"))
    )
    (net (code "92") (name "unconnected-(U1-ROW3-Pad23)") (class "Default")
      (node (ref "U1") (pin "23") (pinfunction "ROW3_23") (pintype "bidirectional"))
    )
    (net (code "93") (name "unconnected-(U1-ROW4-Pad63)") (class "Default")
      (node (ref "U1") (pin "63") (pinfunction "ROW4_63") (pintype "bidirectional"))
    )
    (net (code "94") (name "unconnected-(U1-SCL-Pad74)") (class "Default")
      (node (ref "U1") (pin "74") (pinfunction "SCL_74") (pintype "bidirectional"))
    )
    (net (code "95") (name "unconnected-(U1-SDA-Pad75)") (class "Default")
      (node (ref "U1") (pin "75") (pinfunction "SDA_75") (pintype "bidirectional"))
    )
    (net (code "96") (name "unconnected-(U1-SIMPRE-Pad54)") (class "Default")
      (node (ref "U1") (pin "54") (pinfunction "SIMPRE_54") (pintype "input"))
    )
    (net (code "97") (name "unconnected-(U1-SPK1N-Pad13)") (class "Default")
      (node (ref "U1") (pin "13") (pinfunction "SPK1N_13") (pintype "output"))
    )
    (net (code "98") (name "unconnected-(U1-SPK1P-Pad53)") (class "Default")
      (node (ref "U1") (pin "53") (pinfunction "SPK1P_53") (pintype "output"))
    )
    (net (code "99") (name "unconnected-(U1-SPK2N-Pad11)") (class "Default")
      (node (ref "U1") (pin "11") (pinfunction "SPK2N_11") (pintype "output"))
    )
    (net (code "100") (name "unconnected-(U1-SPK2P{slash}8Ω-Pad51)") (class "Default")
      (node (ref "U1") (pin "51") (pinfunction "SPK2P/8Ω_51") (pintype "output"))
    )
    (net (code "101") (name "unconnected-(U1-UART_CTS-Pad34)") (class "Default")
      (node (ref "U1") (pin "34") (pinfunction "UART_CTS_34") (pintype "output"))
    )
    (net (code "102") (name "unconnected-(U1-UART_DCD-Pad70)") (class "Default")
      (node (ref "U1") (pin "70") (pinfunction "UART_DCD_70") (pintype "input"))
    )
    (net (code "103") (name "unconnected-(U1-UART_DTR-Pad69)") (class "Default")
      (node (ref "U1") (pin "69") (pinfunction "UART_DTR_69") (pintype "input"))
    )
    (net (code "104") (name "unconnected-(U1-UART_RTS-Pad33)") (class "Default")
      (node (ref "U1") (pin "33") (pinfunction "UART_RTS_33") (pintype "input"))
    )
    (net (code "105") (name "unconnected-(U1-USB_DM-Pad19)") (class "Default")
      (node (ref "U1") (pin "19") (pinfunction "USB_DM_19") (pintype "bidirectional"))
    )
    (net (code "106") (name "unconnected-(U1-USB_DP-Pad59)") (class "Default")
      (node (ref "U1") (pin "59") (pinfunction "USB_DP_59") (pintype "bidirectional"))
    )
    (net (code "107") (name "unconnected-(U4-ADC-Pad2)") (class "Default")
      (node (ref "U4") (pin "2") (pinfunction "ADC_2") (pintype "passive"))
    )
    (net (code "108") (name "unconnected-(U4-CS0-Pad9)") (class "Default")
      (node (ref "U4") (pin "9") (pinfunction "CS0_9") (pintype "input"))
    )
    (net (code "109") (name "unconnected-(U4-IO9-Pad11)") (class "Default")
      (node (ref "U4") (pin "11") (pinfunction "IO9_11") (pintype "bidirectional"))
    )
    (net (code "110") (name "unconnected-(U4-IO10-Pad12)") (class "Default")
      (node (ref "U4") (pin "12") (pinfunction "IO10_12") (pintype "bidirectional"))
    )
    (net (code "111") (name "unconnected-(U4-MISO-Pad10)") (class "Default")
      (node (ref "U4") (pin "10") (pinfunction "MISO_10") (pintype "bidirectional"))
    )
    (net (code "112") (name "unconnected-(U4-MOSI-Pad13)") (class "Default")
      (node (ref "U4") (pin "13") (pinfunction "MOSI_13") (pintype "bidirectional"))
    )
    (net (code "113") (name "unconnected-(U4-SCLK-Pad14)") (class "Default")
      (node (ref "U4") (pin "14") (pinfunction "SCLK_14") (pintype "input"))
    )
    (net (code "114") (name "unconnected-(U5-CHR0-Pad15)") (class "Default")
      (node (ref "U5") (pin "15") (pinfunction "CHR0_15") (pintype "output"))
    )
    (net (code "115") (name "unconnected-(U5-CHR1-Pad14)") (class "Default")
      (node (ref "U5") (pin "14") (pinfunction "CHR1_14") (pintype "output"))
    )
    (net (code "116") (name "unconnected-(U5-CHREN-Pad13)") (class "Default")
      (node (ref "U5") (pin "13") (pinfunction "CHREN_13") (pintype "output"))
    )
    (net (code "117") (name "unconnected-(U5-CTS-Pad23)") (class "Default")
      (node (ref "U5") (pin "23") (pinfunction "CTS_23") (pintype "input"))
    )
    (net (code "118") (name "unconnected-(U5-DCD-Pad1)") (class "Default")
      (node (ref "U5") (pin "1") (pinfunction "DCD_1") (pintype "input"))
    )
    (net (code "119") (name "unconnected-(U5-DSR-Pad27)") (class "Default")
      (node (ref "U5") (pin "27") (pinfunction "DSR_27") (pintype "input"))
    )
    (net (code "120") (name "unconnected-(U5-GPIO.2{slash}RS485-Pad17)") (class "Default")
      (node (ref "U5") (pin "17") (pinfunction "GPIO.2/RS485_17") (pintype "bidirectional"))
    )
    (net (code "121") (name "unconnected-(U5-GPIO.3{slash}WAKEUP-Pad16)") (class "Default")
      (node (ref "U5") (pin "16") (pinfunction "GPIO.3/WAKEUP_16") (pintype "bidirectional"))
    )
    (net (code "122") (name "unconnected-(U5-GPIO.4-Pad22)") (class "Default")
      (node (ref "U5") (pin "22") (pinfunction "GPIO.4_22") (pintype "bidirectional"))
    )
    (net (code "123") (name "unconnected-(U5-GPIO.5-Pad21)") (class "Default")
      (node (ref "U5") (pin "21") (pinfunction "GPIO.5_21") (pintype "bidirectional"))
    )
    (net (code "124") (name "unconnected-(U5-GPIO.6-Pad20)") (class "Default")
      (node (ref "U5") (pin "20") (pinfunction "GPIO.6_20") (pintype "bidirectional"))
    )
    (net (code "125") (name "unconnected-(U5-NC-Pad10)") (class "Default")
      (node (ref "U5") (pin "10") (pinfunction "NC_10") (pintype "no_connect"))
    )
    (net (code "126") (name "unconnected-(U5-RI{slash}CLK-Pad2)") (class "Default")
      (node (ref "U5") (pin "2") (pinfunction "RI/CLK_2") (pintype "bidirectional"))
    )
    (net (code "127") (name "unconnected-(U5-SUSPEND-Pad12)") (class "Default")
      (node (ref "U5") (pin "12") (pinfunction "SUSPEND_12") (pintype "output"))
    )
    (net (code "128") (name "unconnected-(U5-~{SUSPEND}-Pad11)") (class "Default")
      (node (ref "U5") (pin "11") (pinfunction "~{SUSPEND}_11") (pintype "output"))
    )
    (net (code "129") (name "unconnected-(U6-NC-Pad2)") (class "Default")
      (node (ref "U6") (pin "2") (pinfunction "NC_2") (pintype "no_connect"))
    )
    (net (code "130") (name "unconnected-(X2-5-PadC6)") (class "Default")
      (node (ref "X2") (pin "C6") (pinfunction "5_C6") (pintype "passive"))
    )
  )
)
